# switch_board.net
KiCad netlist of a schematic drawn in EAGLE
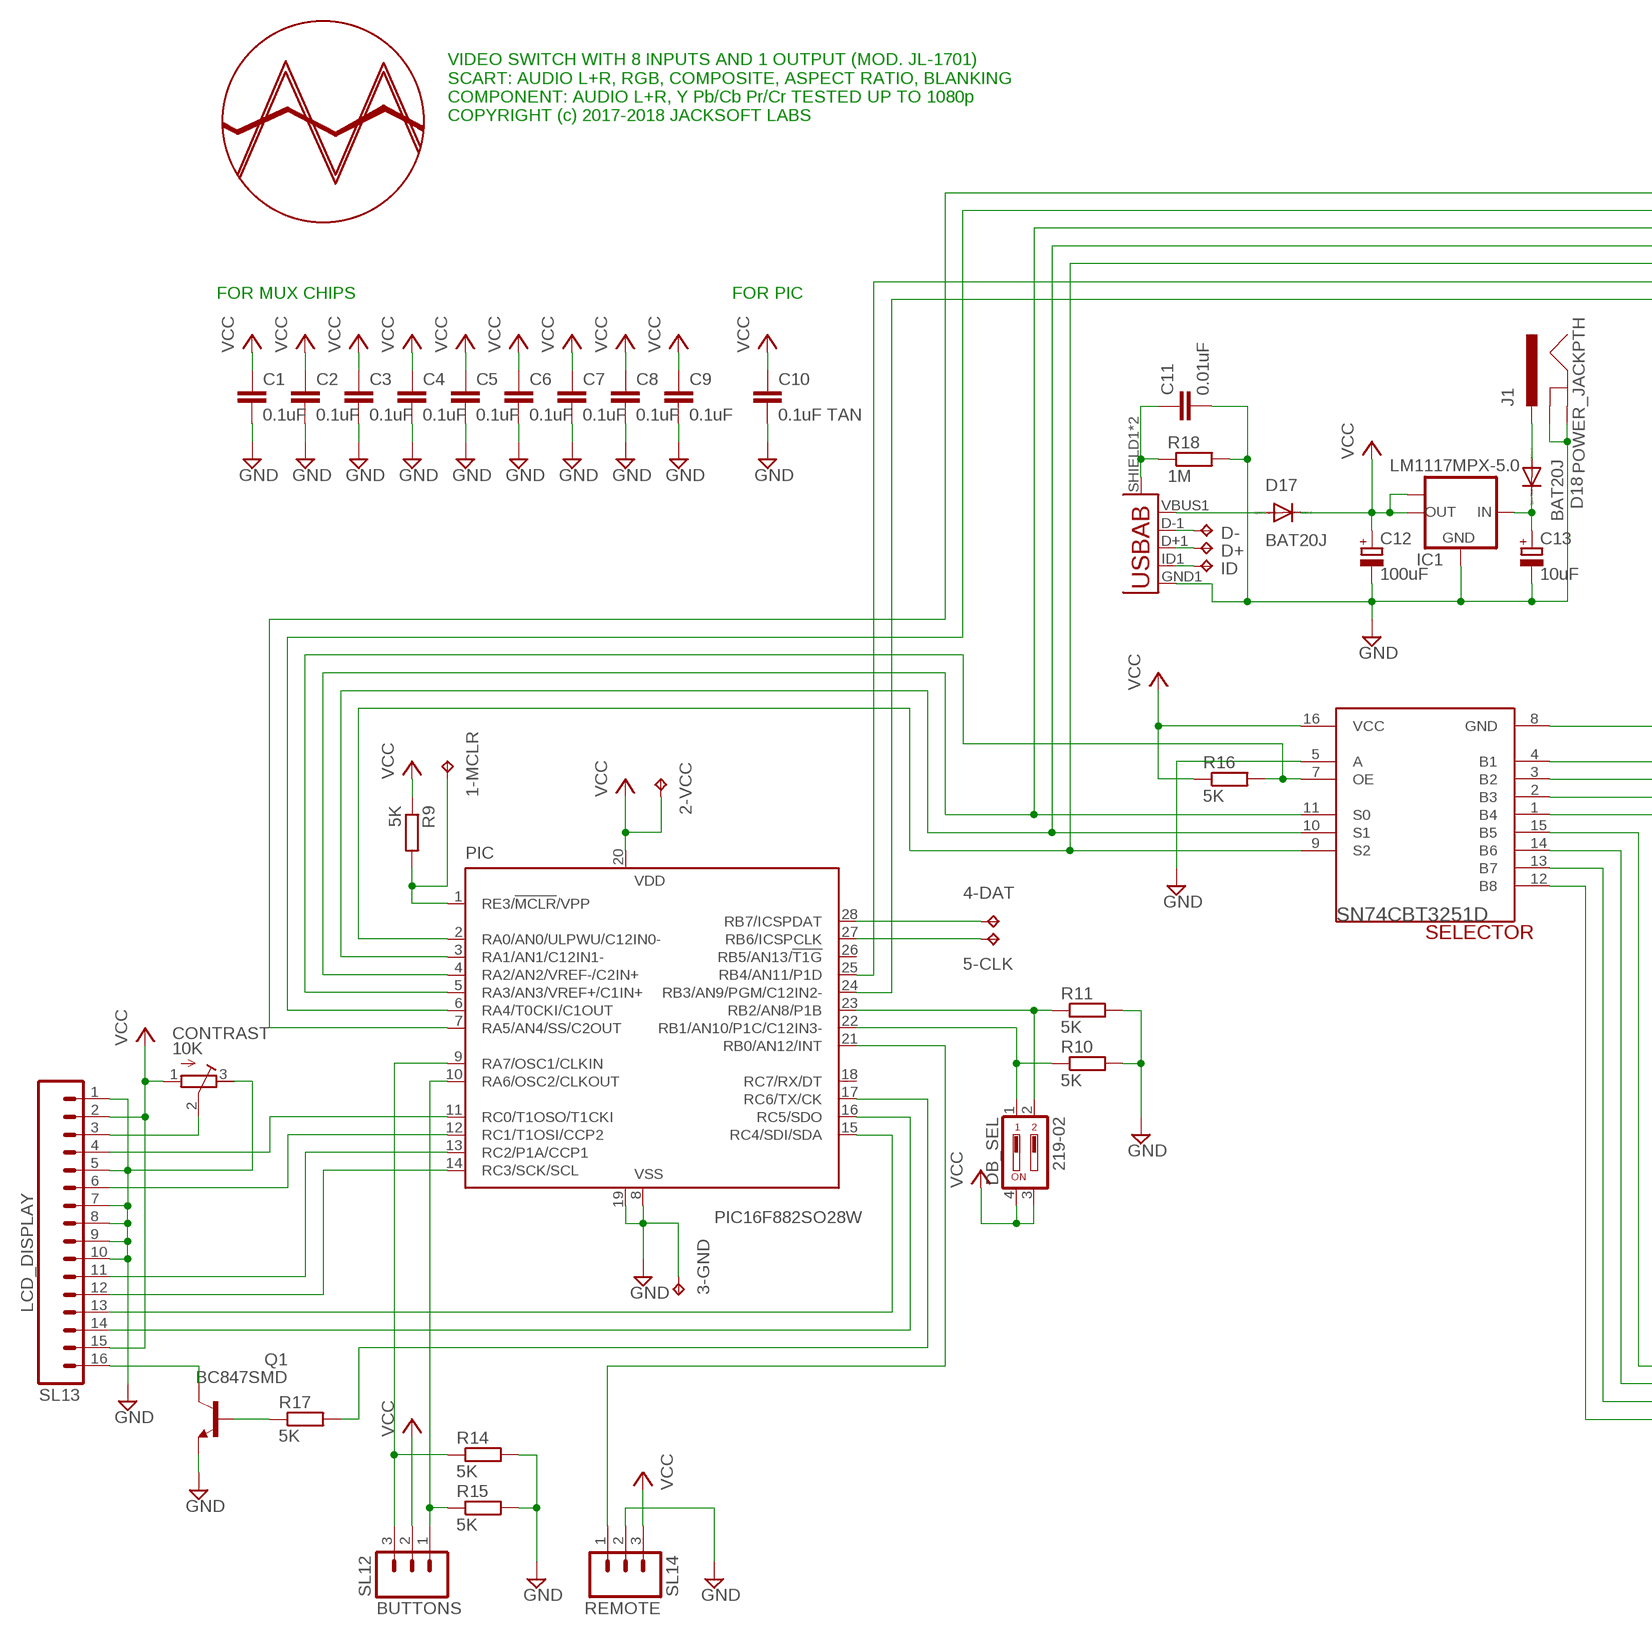
[diagram p0: schematic, sheet 1, part 1 of 2]
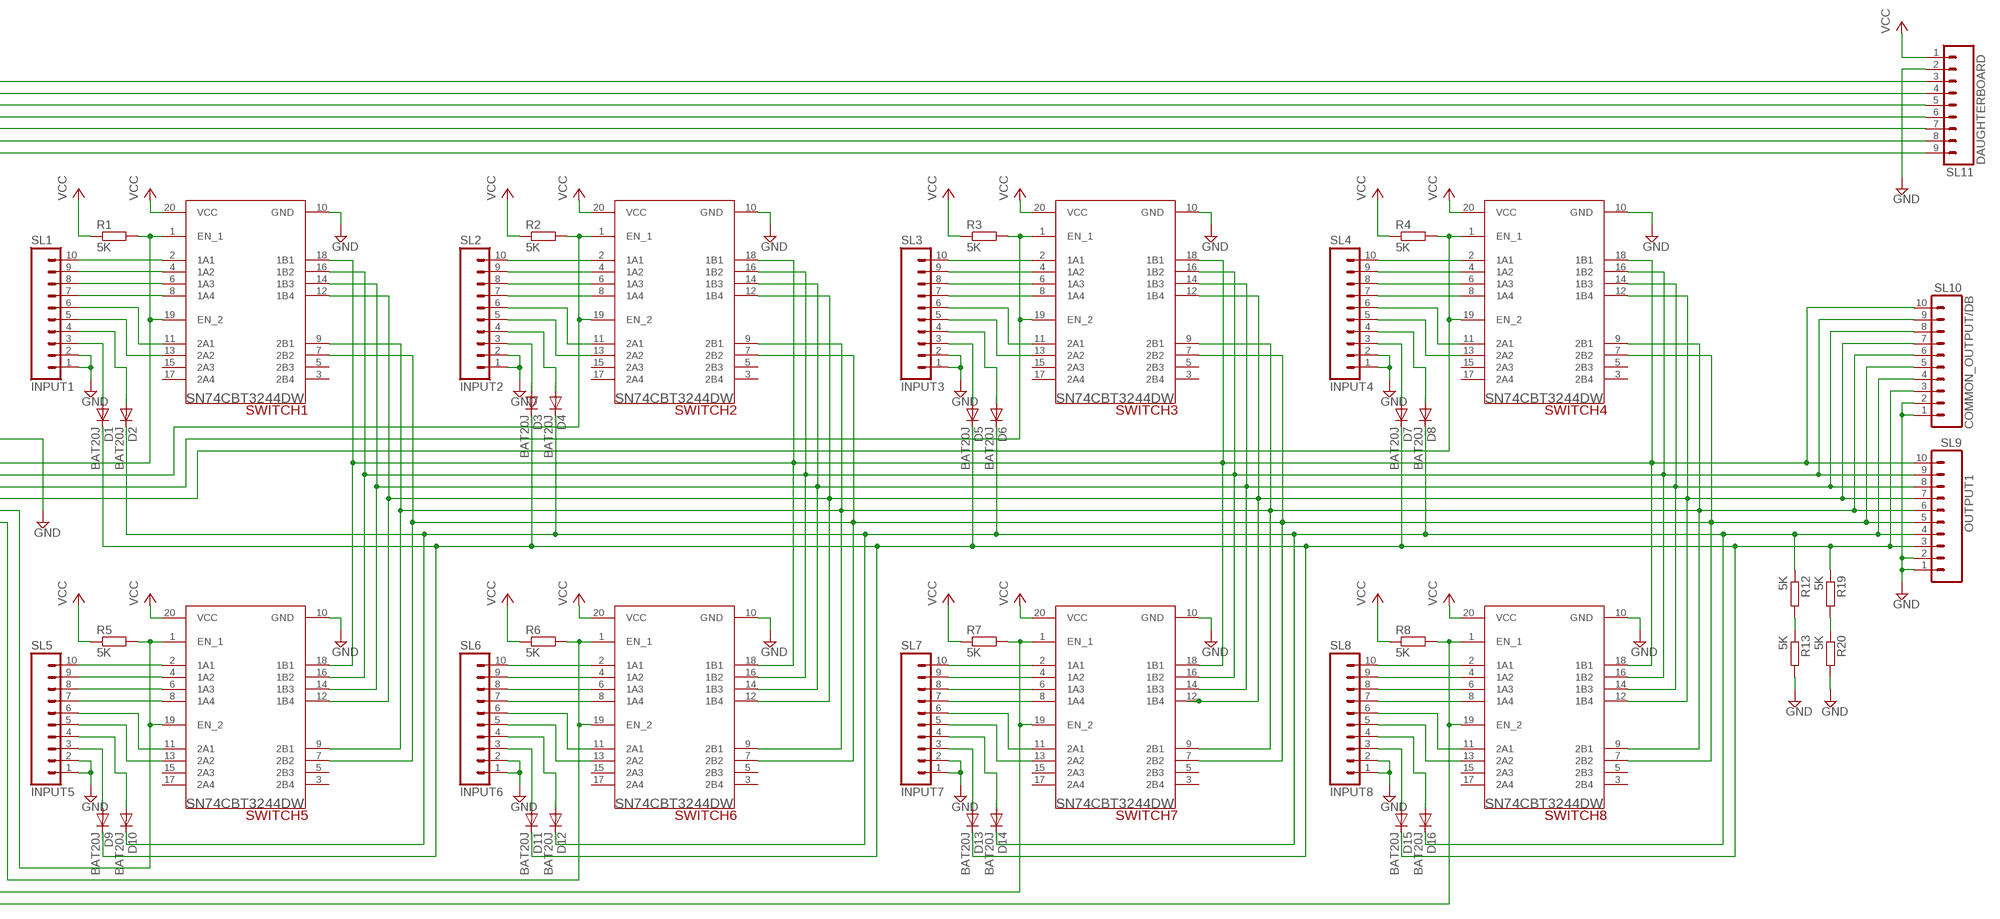
[diagram p1: schematic, sheet 1, part 2 of 2]

(export (version "E")
  (design (tool "Eeschema 10.0.6"))
  (components
    (comp (ref "1-MCLR")
      (value "TPB1,27")
      (footprint "eagle-import:B1,27")
      (libsource (lib "eagle-import") (part "TPB1,27"))
    )
    (comp (ref "2-VCC")
      (value "TPB1,27")
      (footprint "eagle-import:B1,27")
      (libsource (lib "eagle-import") (part "TPB1,27"))
    )
    (comp (ref "3-GND")
      (value "TPB1,27")
      (footprint "eagle-import:B1,27")
      (libsource (lib "eagle-import") (part "TPB1,27"))
    )
    (comp (ref "4-DAT")
      (value "TPB1,27")
      (footprint "eagle-import:B1,27")
      (libsource (lib "eagle-import") (part "TPB1,27"))
    )
    (comp (ref "5-CLK")
      (value "TPB1,27")
      (footprint "eagle-import:B1,27")
      (libsource (lib "eagle-import") (part "TPB1,27"))
    )
    (comp (ref "C1")
      (value "0.1uF")
      (footprint "eagle-import:C0603")
      (libsource (lib "eagle-import") (part "C-EUC0603"))
    )
    (comp (ref "C2")
      (value "0.1uF")
      (footprint "eagle-import:C0603")
      (libsource (lib "eagle-import") (part "C-EUC0603"))
    )
    (comp (ref "C3")
      (value "0.1uF")
      (footprint "eagle-import:C0603")
      (libsource (lib "eagle-import") (part "C-EUC0603"))
    )
    (comp (ref "C4")
      (value "0.1uF")
      (footprint "eagle-import:C0603")
      (libsource (lib "eagle-import") (part "C-EUC0603"))
    )
    (comp (ref "C5")
      (value "0.1uF")
      (footprint "eagle-import:C0603")
      (libsource (lib "eagle-import") (part "C-EUC0603"))
    )
    (comp (ref "C6")
      (value "0.1uF")
      (footprint "eagle-import:C0603")
      (libsource (lib "eagle-import") (part "C-EUC0603"))
    )
    (comp (ref "C7")
      (value "0.1uF")
      (footprint "eagle-import:C0603")
      (libsource (lib "eagle-import") (part "C-EUC0603"))
    )
    (comp (ref "C8")
      (value "0.1uF")
      (footprint "eagle-import:C0603")
      (libsource (lib "eagle-import") (part "C-EUC0603"))
    )
    (comp (ref "C9")
      (value "0.1uF")
      (footprint "eagle-import:C0603")
      (libsource (lib "eagle-import") (part "C-EUC0603"))
    )
    (comp (ref "C10")
      (value "0.1uF TAN")
      (footprint "eagle-import:C3216")
      (libsource (lib "eagle-import") (part "C-EUC3216"))
    )
    (comp (ref "C11")
      (value "0.01uF")
      (footprint "eagle-import:C0603")
      (libsource (lib "eagle-import") (part "C-EUC0603"))
    )
    (comp (ref "C12")
      (value "100uF")
      (footprint "eagle-import:153CLV-0405")
      (libsource (lib "eagle-import") (part "CPOL-EU153CLV-0405"))
    )
    (comp (ref "C13")
      (value "10uF")
      (footprint "eagle-import:153CLV-0405")
      (libsource (lib "eagle-import") (part "CPOL-EU153CLV-0405"))
    )
    (comp (ref "CONTRAST")
      (value "10K")
      (footprint "eagle-import:RTRIM3304W")
      (libsource (lib "eagle-import") (part "R-TRIMM3304W"))
    )
    (comp (ref "D+")
      (value "TPTP06R")
      (footprint "eagle-import:TP06R")
      (libsource (lib "eagle-import") (part "TPTP06R"))
    )
    (comp (ref "D-")
      (value "TPTP06R")
      (footprint "eagle-import:TP06R")
      (libsource (lib "eagle-import") (part "TPTP06R"))
    )
    (comp (ref "D1")
      (value "BAT20J")
      (footprint "eagle-import:SOD323-W")
      (libsource (lib "eagle-import") (part "DIODE-SOD323-W"))
    )
    (comp (ref "D2")
      (value "BAT20J")
      (footprint "eagle-import:SOD323-W")
      (libsource (lib "eagle-import") (part "DIODE-SOD323-W"))
    )
    (comp (ref "D3")
      (value "BAT20J")
      (footprint "eagle-import:SOD323-W")
      (libsource (lib "eagle-import") (part "DIODE-SOD323-W"))
    )
    (comp (ref "D4")
      (value "BAT20J")
      (footprint "eagle-import:SOD323-W")
      (libsource (lib "eagle-import") (part "DIODE-SOD323-W"))
    )
    (comp (ref "D5")
      (value "BAT20J")
      (footprint "eagle-import:SOD323-W")
      (libsource (lib "eagle-import") (part "DIODE-SOD323-W"))
    )
    (comp (ref "D6")
      (value "BAT20J")
      (footprint "eagle-import:SOD323-W")
      (libsource (lib "eagle-import") (part "DIODE-SOD323-W"))
    )
    (comp (ref "D7")
      (value "BAT20J")
      (footprint "eagle-import:SOD323-W")
      (libsource (lib "eagle-import") (part "DIODE-SOD323-W"))
    )
    (comp (ref "D8")
      (value "BAT20J")
      (footprint "eagle-import:SOD323-W")
      (libsource (lib "eagle-import") (part "DIODE-SOD323-W"))
    )
    (comp (ref "D9")
      (value "BAT20J")
      (footprint "eagle-import:SOD323-W")
      (libsource (lib "eagle-import") (part "DIODE-SOD323-W"))
    )
    (comp (ref "D10")
      (value "BAT20J")
      (footprint "eagle-import:SOD323-W")
      (libsource (lib "eagle-import") (part "DIODE-SOD323-W"))
    )
    (comp (ref "D11")
      (value "BAT20J")
      (footprint "eagle-import:SOD323-W")
      (libsource (lib "eagle-import") (part "DIODE-SOD323-W"))
    )
    (comp (ref "D12")
      (value "BAT20J")
      (footprint "eagle-import:SOD323-W")
      (libsource (lib "eagle-import") (part "DIODE-SOD323-W"))
    )
    (comp (ref "D13")
      (value "BAT20J")
      (footprint "eagle-import:SOD323-W")
      (libsource (lib "eagle-import") (part "DIODE-SOD323-W"))
    )
    (comp (ref "D14")
      (value "BAT20J")
      (footprint "eagle-import:SOD323-W")
      (libsource (lib "eagle-import") (part "DIODE-SOD323-W"))
    )
    (comp (ref "D15")
      (value "BAT20J")
      (footprint "eagle-import:SOD323-W")
      (libsource (lib "eagle-import") (part "DIODE-SOD323-W"))
    )
    (comp (ref "D16")
      (value "BAT20J")
      (footprint "eagle-import:SOD323-W")
      (libsource (lib "eagle-import") (part "DIODE-SOD323-W"))
    )
    (comp (ref "D17")
      (value "BAT20J")
      (footprint "eagle-import:SOD323-W")
      (libsource (lib "eagle-import") (part "DIODE-SOD323-W"))
    )
    (comp (ref "D18")
      (value "BAT20J")
      (footprint "eagle-import:SOD323-W")
      (libsource (lib "eagle-import") (part "DIODE-SOD323-W"))
    )
    (comp (ref "DB_SEL")
      (value "219-02")
      (footprint "eagle-import:CTS-219-02")
      (libsource (lib "eagle-import") (part "219-02"))
    )
    (comp (ref "IC1")
      (value "LM1117MPX-5.0")
      (footprint "eagle-import:SOT223")
      (libsource (lib "eagle-import") (part "LM1117MPX-5.0"))
    )
    (comp (ref "ID")
      (value "TPTP06R")
      (footprint "eagle-import:TP06R")
      (libsource (lib "eagle-import") (part "TPTP06R"))
    )
    (comp (ref "J1")
      (value "POWER_JACKPTH")
      (footprint "eagle-import:POWER_JACK_PTH")
      (libsource (lib "eagle-import") (part "POWER_JACKPTH"))
    )
    (comp (ref "PIC")
      (value "PIC16F882SO28W")
      (footprint "eagle-import:16F882")
      (libsource (lib "eagle-import") (part "PIC16F882SO28W"))
    )
    (comp (ref "Q1")
      (value "BC847SMD")
      (footprint "eagle-import:SOT23")
      (libsource (lib "eagle-import") (part "BC847SMD"))
    )
    (comp (ref "R1")
      (value "5K")
      (footprint "eagle-import:R0603")
      (libsource (lib "eagle-import") (part "R-EU_R0603"))
    )
    (comp (ref "R2")
      (value "5K")
      (footprint "eagle-import:R0603")
      (libsource (lib "eagle-import") (part "R-EU_R0603"))
    )
    (comp (ref "R3")
      (value "5K")
      (footprint "eagle-import:R0603")
      (libsource (lib "eagle-import") (part "R-EU_R0603"))
    )
    (comp (ref "R4")
      (value "5K")
      (footprint "eagle-import:R0603")
      (libsource (lib "eagle-import") (part "R-EU_R0603"))
    )
    (comp (ref "R5")
      (value "5K")
      (footprint "eagle-import:R0603")
      (libsource (lib "eagle-import") (part "R-EU_R0603"))
    )
    (comp (ref "R6")
      (value "5K")
      (footprint "eagle-import:R0603")
      (libsource (lib "eagle-import") (part "R-EU_R0603"))
    )
    (comp (ref "R7")
      (value "5K")
      (footprint "eagle-import:R0603")
      (libsource (lib "eagle-import") (part "R-EU_R0603"))
    )
    (comp (ref "R8")
      (value "5K")
      (footprint "eagle-import:R0603")
      (libsource (lib "eagle-import") (part "R-EU_R0603"))
    )
    (comp (ref "R9")
      (value "5K")
      (footprint "eagle-import:R0603")
      (libsource (lib "eagle-import") (part "R-EU_R0603"))
    )
    (comp (ref "R10")
      (value "5K")
      (footprint "eagle-import:R0603")
      (libsource (lib "eagle-import") (part "R-EU_R0603"))
    )
    (comp (ref "R11")
      (value "5K")
      (footprint "eagle-import:R0603")
      (libsource (lib "eagle-import") (part "R-EU_R0603"))
    )
    (comp (ref "R12")
      (value "5K")
      (footprint "eagle-import:R0603")
      (libsource (lib "eagle-import") (part "R-EU_R0603"))
    )
    (comp (ref "R13")
      (value "5K")
      (footprint "eagle-import:R0603")
      (libsource (lib "eagle-import") (part "R-EU_R0603"))
    )
    (comp (ref "R14")
      (value "5K")
      (footprint "eagle-import:R0603")
      (libsource (lib "eagle-import") (part "R-EU_R0603"))
    )
    (comp (ref "R15")
      (value "5K")
      (footprint "eagle-import:R0603")
      (libsource (lib "eagle-import") (part "R-EU_R0603"))
    )
    (comp (ref "R16")
      (value "5K")
      (footprint "eagle-import:R0603")
      (libsource (lib "eagle-import") (part "R-EU_R0603"))
    )
    (comp (ref "R17")
      (value "5K")
      (footprint "eagle-import:R0603")
      (libsource (lib "eagle-import") (part "R-EU_R0603"))
    )
    (comp (ref "R18")
      (value "1M")
      (footprint "eagle-import:R0603")
      (libsource (lib "eagle-import") (part "R-EU_R0603"))
    )
    (comp (ref "R19")
      (value "5K")
      (footprint "eagle-import:R0603")
      (libsource (lib "eagle-import") (part "R-EU_R0603"))
    )
    (comp (ref "R20")
      (value "5K")
      (footprint "eagle-import:R0603")
      (libsource (lib "eagle-import") (part "R-EU_R0603"))
    )
    (comp (ref "SELECTOR")
      (value "SN74CBT3251D")
      (footprint "eagle-import:SOIC127P1032X265-16N")
      (libsource (lib "eagle-import") (part "SN74CBT3251D"))
    )
    (comp (ref "SL1")
      (value "INPUT1")
      (footprint "eagle-import:10P")
      (libsource (lib "eagle-import") (part "M10"))
    )
    (comp (ref "SL2")
      (value "INPUT2")
      (footprint "eagle-import:10P")
      (libsource (lib "eagle-import") (part "M10"))
    )
    (comp (ref "SL3")
      (value "INPUT3")
      (footprint "eagle-import:10P")
      (libsource (lib "eagle-import") (part "M10"))
    )
    (comp (ref "SL4")
      (value "INPUT4")
      (footprint "eagle-import:10P")
      (libsource (lib "eagle-import") (part "M10"))
    )
    (comp (ref "SL5")
      (value "INPUT5")
      (footprint "eagle-import:10P")
      (libsource (lib "eagle-import") (part "M10"))
    )
    (comp (ref "SL6")
      (value "INPUT6")
      (footprint "eagle-import:10P")
      (libsource (lib "eagle-import") (part "M10"))
    )
    (comp (ref "SL7")
      (value "INPUT7")
      (footprint "eagle-import:10P")
      (libsource (lib "eagle-import") (part "M10"))
    )
    (comp (ref "SL8")
      (value "INPUT8")
      (footprint "eagle-import:10P")
      (libsource (lib "eagle-import") (part "M10"))
    )
    (comp (ref "SL9")
      (value "OUTPUT1")
      (footprint "eagle-import:10P")
      (libsource (lib "eagle-import") (part "M10"))
    )
    (comp (ref "SL10")
      (value "COMMON_OUTPUT/DB")
      (footprint "eagle-import:10P")
      (libsource (lib "eagle-import") (part "M10"))
    )
    (comp (ref "SL11")
      (value "DAUGHTERBOARD")
      (footprint "eagle-import:09P")
      (libsource (lib "eagle-import") (part "M09"))
    )
    (comp (ref "SL12")
      (value "BUTTONS")
      (footprint "eagle-import:03P")
      (libsource (lib "eagle-import") (part "M03"))
    )
    (comp (ref "SL13")
      (value "LCD_DISPLAY")
      (footprint "eagle-import:16P")
      (libsource (lib "eagle-import") (part "M16"))
    )
    (comp (ref "SL14")
      (value "REMOTE")
      (footprint "eagle-import:03P")
      (libsource (lib "eagle-import") (part "M03"))
    )
    (comp (ref "SWITCH1")
      (value "SN74CBT3244DW")
      (footprint "eagle-import:SOIC127P1032X265-20N")
      (libsource (lib "eagle-import") (part "SN74CBT3244DW"))
    )
    (comp (ref "SWITCH2")
      (value "SN74CBT3244DW")
      (footprint "eagle-import:SOIC127P1032X265-20N")
      (libsource (lib "eagle-import") (part "SN74CBT3244DW"))
    )
    (comp (ref "SWITCH3")
      (value "SN74CBT3244DW")
      (footprint "eagle-import:SOIC127P1032X265-20N")
      (libsource (lib "eagle-import") (part "SN74CBT3244DW"))
    )
    (comp (ref "SWITCH4")
      (value "SN74CBT3244DW")
      (footprint "eagle-import:SOIC127P1032X265-20N")
      (libsource (lib "eagle-import") (part "SN74CBT3244DW"))
    )
    (comp (ref "SWITCH5")
      (value "SN74CBT3244DW")
      (footprint "eagle-import:SOIC127P1032X265-20N")
      (libsource (lib "eagle-import") (part "SN74CBT3244DW"))
    )
    (comp (ref "SWITCH6")
      (value "SN74CBT3244DW")
      (footprint "eagle-import:SOIC127P1032X265-20N")
      (libsource (lib "eagle-import") (part "SN74CBT3244DW"))
    )
    (comp (ref "SWITCH7")
      (value "SN74CBT3244DW")
      (footprint "eagle-import:SOIC127P1032X265-20N")
      (libsource (lib "eagle-import") (part "SN74CBT3244DW"))
    )
    (comp (ref "SWITCH8")
      (value "SN74CBT3244DW")
      (footprint "eagle-import:SOIC127P1032X265-20N")
      (libsource (lib "eagle-import") (part "SN74CBT3244DW"))
    )
    (comp (ref "U$1")
      (value "JACKSOFTLABS-LOGOLONGTEXT")
      (footprint "eagle-import:LOGO-LONGTEXT")
      (libsource (lib "eagle-import") (part "JACKSOFTLABS-LOGOLONGTEXT"))
    )
    (comp (ref "USB")
      (value "USB_POWER")
      (footprint "eagle-import:USB-MICRO-SMD")
      (libsource (lib "eagle-import") (part "MICROUSB{dblquote}{dblquote}"))
    )
  )
  (nets
    (net (code "1") (name "GND") (class "Default")
      (node (ref "3-GND") (pin "TP") (pinfunction "TP_TP") (pintype "input"))
      (node (ref "C1") (pin "2") (pinfunction "2_2") (pintype "passive"))
      (node (ref "C10") (pin "2") (pinfunction "2_2") (pintype "passive"))
      (node (ref "C11") (pin "2") (pinfunction "2_2") (pintype "passive"))
      (node (ref "C12") (pin "-") (pinfunction "-_-") (pintype "passive"))
      (node (ref "C13") (pin "-") (pinfunction "-_-") (pintype "passive"))
      (node (ref "C2") (pin "2") (pinfunction "2_2") (pintype "passive"))
      (node (ref "C3") (pin "2") (pinfunction "2_2") (pintype "passive"))
      (node (ref "C4") (pin "2") (pinfunction "2_2") (pintype "passive"))
      (node (ref "C5") (pin "2") (pinfunction "2_2") (pintype "passive"))
      (node (ref "C6") (pin "2") (pinfunction "2_2") (pintype "passive"))
      (node (ref "C7") (pin "2") (pinfunction "2_2") (pintype "passive"))
      (node (ref "C8") (pin "2") (pinfunction "2_2") (pintype "passive"))
      (node (ref "C9") (pin "2") (pinfunction "2_2") (pintype "passive"))
      (node (ref "CONTRAST") (pin "3") (pinfunction "E_3") (pintype "passive"))
      (node (ref "IC1") (pin "1") (pinfunction "GND_1") (pintype "input"))
      (node (ref "J1") (pin "GND") (pinfunction "GND_GND") (pintype "bidirectional"))
      (node (ref "J1") (pin "GNDBREAK") (pinfunction "GNDBREAK_GNDBREAK") (pintype "bidirectional"))
      (node (ref "PIC") (pin "19") (pinfunction "VSS_19") (pintype "power_in"))
      (node (ref "PIC") (pin "8") (pinfunction "VSS_8") (pintype "power_in"))
      (node (ref "Q1") (pin "2") (pinfunction "E_2") (pintype "passive"))
      (node (ref "R10") (pin "2") (pinfunction "2_2") (pintype "passive"))
      (node (ref "R11") (pin "2") (pinfunction "2_2") (pintype "passive"))
      (node (ref "R13") (pin "2") (pinfunction "2_2") (pintype "passive"))
      (node (ref "R14") (pin "2") (pinfunction "2_2") (pintype "passive"))
      (node (ref "R15") (pin "2") (pinfunction "2_2") (pintype "passive"))
      (node (ref "R18") (pin "2") (pinfunction "2_2") (pintype "passive"))
      (node (ref "R20") (pin "2") (pinfunction "2_2") (pintype "passive"))
      (node (ref "SELECTOR") (pin "5") (pinfunction "A_5") (pintype "input"))
      (node (ref "SELECTOR") (pin "8") (pinfunction "GND_8") (pintype "input"))
      (node (ref "SL1") (pin "1") (pinfunction "1_1") (pintype "passive"))
      (node (ref "SL1") (pin "2") (pinfunction "2_2") (pintype "passive"))
      (node (ref "SL10") (pin "1") (pinfunction "1_1") (pintype "passive"))
      (node (ref "SL10") (pin "2") (pinfunction "2_2") (pintype "passive"))
      (node (ref "SL11") (pin "2") (pinfunction "2_2") (pintype "passive"))
      (node (ref "SL13") (pin "1") (pinfunction "1_1") (pintype "passive"))
      (node (ref "SL13") (pin "10") (pinfunction "10_10") (pintype "passive"))
      (node (ref "SL13") (pin "5") (pinfunction "5_5") (pintype "passive"))
      (node (ref "SL13") (pin "7") (pinfunction "7_7") (pintype "passive"))
      (node (ref "SL13") (pin "8") (pinfunction "8_8") (pintype "passive"))
      (node (ref "SL13") (pin "9") (pinfunction "9_9") (pintype "passive"))
      (node (ref "SL14") (pin "2") (pinfunction "2_2") (pintype "passive"))
      (node (ref "SL2") (pin "1") (pinfunction "1_1") (pintype "passive"))
      (node (ref "SL2") (pin "2") (pinfunction "2_2") (pintype "passive"))
      (node (ref "SL3") (pin "1") (pinfunction "1_1") (pintype "passive"))
      (node (ref "SL3") (pin "2") (pinfunction "2_2") (pintype "passive"))
      (node (ref "SL4") (pin "1") (pinfunction "1_1") (pintype "passive"))
      (node (ref "SL4") (pin "2") (pinfunction "2_2") (pintype "passive"))
      (node (ref "SL5") (pin "1") (pinfunction "1_1") (pintype "passive"))
      (node (ref "SL5") (pin "2") (pinfunction "2_2") (pintype "passive"))
      (node (ref "SL6") (pin "1") (pinfunction "1_1") (pintype "passive"))
      (node (ref "SL6") (pin "2") (pinfunction "2_2") (pintype "passive"))
      (node (ref "SL7") (pin "1") (pinfunction "1_1") (pintype "passive"))
      (node (ref "SL7") (pin "2") (pinfunction "2_2") (pintype "passive"))
      (node (ref "SL8") (pin "1") (pinfunction "1_1") (pintype "passive"))
      (node (ref "SL8") (pin "2") (pinfunction "2_2") (pintype "passive"))
      (node (ref "SL9") (pin "1") (pinfunction "1_1") (pintype "passive"))
      (node (ref "SL9") (pin "2") (pinfunction "2_2") (pintype "passive"))
      (node (ref "SWITCH1") (pin "10") (pinfunction "GND_10") (pintype "input"))
      (node (ref "SWITCH2") (pin "10") (pinfunction "GND_10") (pintype "input"))
      (node (ref "SWITCH3") (pin "10") (pinfunction "GND_10") (pintype "input"))
      (node (ref "SWITCH4") (pin "10") (pinfunction "GND_10") (pintype "input"))
      (node (ref "SWITCH5") (pin "10") (pinfunction "GND_10") (pintype "input"))
      (node (ref "SWITCH6") (pin "10") (pinfunction "GND_10") (pintype "input"))
      (node (ref "SWITCH7") (pin "10") (pinfunction "GND_10") (pintype "input"))
      (node (ref "SWITCH8") (pin "10") (pinfunction "GND_10") (pintype "input"))
      (node (ref "USB") (pin "GND1") (pinfunction "GND_GND1") (pintype "bidirectional"))
    )
    (net (code "2") (name "Net-(C11-Pad1)") (class "Default")
      (node (ref "C11") (pin "1") (pinfunction "1_1") (pintype "passive"))
      (node (ref "R18") (pin "1") (pinfunction "1_1") (pintype "passive"))
      (node (ref "USB") (pin "SHIELD1") (pinfunction "SHIELD_SHIELD1") (pintype "bidirectional"))
      (node (ref "USB") (pin "SHIELD2") (pinfunction "SHIELD_SHIELD2") (pintype "bidirectional"))
    )
    (net (code "3") (name "Net-(CONTRAST-S)") (class "Default")
      (node (ref "CONTRAST") (pin "2") (pinfunction "S_2") (pintype "passive"))
      (node (ref "SL13") (pin "3") (pinfunction "3_3") (pintype "passive"))
    )
    (net (code "4") (name "Net-(D1-PadA)") (class "Default")
      (node (ref "D1") (pin "A") (pinfunction "A_A") (pintype "passive"))
      (node (ref "SL1") (pin "3") (pinfunction "3_3") (pintype "passive"))
    )
    (net (code "5") (name "Net-(D1-PadC)") (class "Default")
      (node (ref "D1") (pin "C") (pinfunction "C_C") (pintype "passive"))
      (node (ref "D11") (pin "C") (pinfunction "C_C") (pintype "passive"))
      (node (ref "D13") (pin "C") (pinfunction "C_C") (pintype "passive"))
      (node (ref "D15") (pin "C") (pinfunction "C_C") (pintype "passive"))
      (node (ref "D3") (pin "C") (pinfunction "C_C") (pintype "passive"))
      (node (ref "D5") (pin "C") (pinfunction "C_C") (pintype "passive"))
      (node (ref "D7") (pin "C") (pinfunction "C_C") (pintype "passive"))
      (node (ref "D9") (pin "C") (pinfunction "C_C") (pintype "passive"))
      (node (ref "R19") (pin "1") (pinfunction "1_1") (pintype "passive"))
      (node (ref "SL10") (pin "3") (pinfunction "3_3") (pintype "passive"))
      (node (ref "SL9") (pin "3") (pinfunction "3_3") (pintype "passive"))
    )
    (net (code "6") (name "Net-(D2-PadA)") (class "Default")
      (node (ref "D2") (pin "A") (pinfunction "A_A") (pintype "passive"))
      (node (ref "SL1") (pin "4") (pinfunction "4_4") (pintype "passive"))
    )
    (net (code "7") (name "Net-(D3-PadA)") (class "Default")
      (node (ref "D3") (pin "A") (pinfunction "A_A") (pintype "passive"))
      (node (ref "SL2") (pin "3") (pinfunction "3_3") (pintype "passive"))
    )
    (net (code "8") (name "Net-(D4-PadA)") (class "Default")
      (node (ref "D4") (pin "A") (pinfunction "A_A") (pintype "passive"))
      (node (ref "SL2") (pin "4") (pinfunction "4_4") (pintype "passive"))
    )
    (net (code "9") (name "Net-(D5-PadA)") (class "Default")
      (node (ref "D5") (pin "A") (pinfunction "A_A") (pintype "passive"))
      (node (ref "SL3") (pin "3") (pinfunction "3_3") (pintype "passive"))
    )
    (net (code "10") (name "Net-(D6-PadA)") (class "Default")
      (node (ref "D6") (pin "A") (pinfunction "A_A") (pintype "passive"))
      (node (ref "SL3") (pin "4") (pinfunction "4_4") (pintype "passive"))
    )
    (net (code "11") (name "Net-(D7-PadA)") (class "Default")
      (node (ref "D7") (pin "A") (pinfunction "A_A") (pintype "passive"))
      (node (ref "SL4") (pin "3") (pinfunction "3_3") (pintype "passive"))
    )
    (net (code "12") (name "Net-(D8-PadA)") (class "Default")
      (node (ref "D8") (pin "A") (pinfunction "A_A") (pintype "passive"))
      (node (ref "SL4") (pin "4") (pinfunction "4_4") (pintype "passive"))
    )
    (net (code "13") (name "Net-(D9-PadA)") (class "Default")
      (node (ref "D9") (pin "A") (pinfunction "A_A") (pintype "passive"))
      (node (ref "SL5") (pin "3") (pinfunction "3_3") (pintype "passive"))
    )
    (net (code "14") (name "Net-(D10-PadA)") (class "Default")
      (node (ref "D10") (pin "A") (pinfunction "A_A") (pintype "passive"))
      (node (ref "SL5") (pin "4") (pinfunction "4_4") (pintype "passive"))
    )
    (net (code "15") (name "Net-(D10-PadC)") (class "Default")
      (node (ref "D10") (pin "C") (pinfunction "C_C") (pintype "passive"))
      (node (ref "D12") (pin "C") (pinfunction "C_C") (pintype "passive"))
      (node (ref "D14") (pin "C") (pinfunction "C_C") (pintype "passive"))
      (node (ref "D16") (pin "C") (pinfunction "C_C") (pintype "passive"))
      (node (ref "D2") (pin "C") (pinfunction "C_C") (pintype "passive"))
      (node (ref "D4") (pin "C") (pinfunction "C_C") (pintype "passive"))
      (node (ref "D6") (pin "C") (pinfunction "C_C") (pintype "passive"))
      (node (ref "D8") (pin "C") (pinfunction "C_C") (pintype "passive"))
      (node (ref "R12") (pin "1") (pinfunction "1_1") (pintype "passive"))
      (node (ref "SL10") (pin "4") (pinfunction "4_4") (pintype "passive"))
      (node (ref "SL9") (pin "4") (pinfunction "4_4") (pintype "passive"))
    )
    (net (code "16") (name "Net-(D11-PadA)") (class "Default")
      (node (ref "D11") (pin "A") (pinfunction "A_A") (pintype "passive"))
      (node (ref "SL6") (pin "3") (pinfunction "3_3") (pintype "passive"))
    )
    (net (code "17") (name "Net-(D12-PadA)") (class "Default")
      (node (ref "D12") (pin "A") (pinfunction "A_A") (pintype "passive"))
      (node (ref "SL6") (pin "4") (pinfunction "4_4") (pintype "passive"))
    )
    (net (code "18") (name "Net-(D13-PadA)") (class "Default")
      (node (ref "D13") (pin "A") (pinfunction "A_A") (pintype "passive"))
      (node (ref "SL7") (pin "3") (pinfunction "3_3") (pintype "passive"))
    )
    (net (code "19") (name "Net-(D14-PadA)") (class "Default")
      (node (ref "D14") (pin "A") (pinfunction "A_A") (pintype "passive"))
      (node (ref "SL7") (pin "4") (pinfunction "4_4") (pintype "passive"))
    )
    (net (code "20") (name "Net-(D15-PadA)") (class "Default")
      (node (ref "D15") (pin "A") (pinfunction "A_A") (pintype "passive"))
      (node (ref "SL8") (pin "3") (pinfunction "3_3") (pintype "passive"))
    )
    (net (code "21") (name "Net-(D16-PadA)") (class "Default")
      (node (ref "D16") (pin "A") (pinfunction "A_A") (pintype "passive"))
      (node (ref "SL8") (pin "4") (pinfunction "4_4") (pintype "passive"))
    )
    (net (code "22") (name "Net-(D18-PadA)") (class "Default")
      (node (ref "D18") (pin "A") (pinfunction "A_A") (pintype "passive"))
      (node (ref "J1") (pin "PWR") (pinfunction "PWR_PWR") (pintype "bidirectional"))
    )
    (net (code "23") (name "Net-(IC1-IN)") (class "Default")
      (node (ref "C13") (pin "+") (pinfunction "+_+") (pintype "passive"))
      (node (ref "D18") (pin "C") (pinfunction "C_C") (pintype "passive"))
      (node (ref "IC1") (pin "3") (pinfunction "IN_3") (pintype "input"))
    )
    (net (code "24") (name "Net-(PIC-RA0{slash}AN0{slash}ULPWU{slash}C12IN0-)") (class "Default")
      (node (ref "PIC") (pin "2") (pinfunction "RA0/AN0/ULPWU/C12IN0-_2") (pintype "bidirectional"))
      (node (ref "SELECTOR") (pin "9") (pinfunction "S2_9") (pintype "input"))
      (node (ref "SL11") (pin "7") (pinfunction "7_7") (pintype "passive"))
    )
    (net (code "25") (name "Net-(PIC-RA1{slash}AN1{slash}C12IN1-)") (class "Default")
      (node (ref "PIC") (pin "3") (pinfunction "RA1/AN1/C12IN1-_3") (pintype "bidirectional"))
      (node (ref "SELECTOR") (pin "10") (pinfunction "S1_10") (pintype "input"))
      (node (ref "SL11") (pin "6") (pinfunction "6_6") (pintype "passive"))
    )
    (net (code "26") (name "Net-(PIC-RA2{slash}AN2{slash}VREF-{slash}C2IN+)") (class "Default")
      (node (ref "PIC") (pin "4") (pinfunction "RA2/AN2/VREF-/C2IN+_4") (pintype "bidirectional"))
      (node (ref "SELECTOR") (pin "11") (pinfunction "S0_11") (pintype "input"))
      (node (ref "SL11") (pin "5") (pinfunction "5_5") (pintype "passive"))
    )
    (net (code "27") (name "Net-(PIC-RA3{slash}AN3{slash}VREF+{slash}C1IN+)") (class "Default")
      (node (ref "PIC") (pin "5") (pinfunction "RA3/AN3/VREF+/C1IN+_5") (pintype "bidirectional"))
      (node (ref "R16") (pin "2") (pinfunction "2_2") (pintype "passive"))
      (node (ref "SELECTOR") (pin "7") (pinfunction "OE_7") (pintype "input"))
    )
    (net (code "28") (name "Net-(PIC-RA4{slash}T0CKI{slash}C1OUT)") (class "Default")
      (node (ref "PIC") (pin "6") (pinfunction "RA4/T0CKI/C1OUT_6") (pintype "bidirectional"))
      (node (ref "SL11") (pin "4") (pinfunction "4_4") (pintype "passive"))
    )
    (net (code "29") (name "Net-(PIC-RA5{slash}AN4{slash}SS{slash}C2OUT)") (class "Default")
      (node (ref "PIC") (pin "7") (pinfunction "RA5/AN4/SS/C2OUT_7") (pintype "bidirectional"))
      (node (ref "SL11") (pin "3") (pinfunction "3_3") (pintype "passive"))
    )
    (net (code "30") (name "Net-(PIC-RA6{slash}OSC2{slash}CLKOUT)") (class "Default")
      (node (ref "PIC") (pin "10") (pinfunction "RA6/OSC2/CLKOUT_10") (pintype "output"))
      (node (ref "R15") (pin "1") (pinfunction "1_1") (pintype "passive"))
      (node (ref "SL12") (pin "1") (pinfunction "1_1") (pintype "passive"))
    )
    (net (code "31") (name "Net-(PIC-RA7{slash}OSC1{slash}CLKIN)") (class "Default")
      (node (ref "PIC") (pin "9") (pinfunction "RA7/OSC1/CLKIN_9") (pintype "input"))
      (node (ref "R14") (pin "1") (pinfunction "1_1") (pintype "passive"))
      (node (ref "SL12") (pin "3") (pinfunction "3_3") (pintype "passive"))
    )
    (net (code "32") (name "Net-(PIC-RB0{slash}AN12{slash}INT)") (class "Default")
      (node (ref "PIC") (pin "21") (pinfunction "RB0/AN12/INT_21") (pintype "bidirectional"))
      (node (ref "SL14") (pin "1") (pinfunction "1_1") (pintype "passive"))
    )
    (net (code "33") (name "Net-(PIC-RB1{slash}AN10{slash}P1C{slash}C12IN3-)") (class "Default")
      (node (ref "DB_SEL") (pin "1") (pinfunction "1_1") (pintype "passive"))
      (node (ref "PIC") (pin "22") (pinfunction "RB1/AN10/P1C/C12IN3-_22") (pintype "bidirectional"))
      (node (ref "R10") (pin "1") (pinfunction "1_1") (pintype "passive"))
    )
    (net (code "34") (name "Net-(PIC-RB2{slash}AN8{slash}P1B)") (class "Default")
      (node (ref "DB_SEL") (pin "2") (pinfunction "2_2") (pintype "passive"))
      (node (ref "PIC") (pin "23") (pinfunction "RB2/AN8/P1B_23") (pintype "bidirectional"))
      (node (ref "R11") (pin "1") (pinfunction "1_1") (pintype "passive"))
    )
    (net (code "35") (name "Net-(PIC-RB3{slash}AN9{slash}PGM{slash}C12IN2-)") (class "Default")
      (node (ref "PIC") (pin "24") (pinfunction "RB3/AN9/PGM/C12IN2-_24") (pintype "bidirectional"))
      (node (ref "SL11") (pin "9") (pinfunction "9_9") (pintype "passive"))
    )
    (net (code "36") (name "Net-(PIC-RB4{slash}AN11{slash}P1D)") (class "Default")
      (node (ref "PIC") (pin "25") (pinfunction "RB4/AN11/P1D_25") (pintype "bidirectional"))
      (node (ref "SL11") (pin "8") (pinfunction "8_8") (pintype "passive"))
    )
    (net (code "37") (name "Net-(PIC-RB6{slash}ICSPCLK)") (class "Default")
      (node (ref "5-CLK") (pin "TP") (pinfunction "TP_TP") (pintype "input"))
      (node (ref "PIC") (pin "27") (pinfunction "RB6/ICSPCLK_27") (pintype "bidirectional"))
    )
    (net (code "38") (name "Net-(PIC-RB7{slash}ICSPDAT)") (class "Default")
      (node (ref "4-DAT") (pin "TP") (pinfunction "TP_TP") (pintype "input"))
      (node (ref "PIC") (pin "28") (pinfunction "RB7/ICSPDAT_28") (pintype "bidirectional"))
    )
    (net (code "39") (name "Net-(PIC-RC0{slash}T1OSO{slash}T1CKI)") (class "Default")
      (node (ref "PIC") (pin "11") (pinfunction "RC0/T1OSO/T1CKI_11") (pintype "bidirectional"))
      (node (ref "SL13") (pin "4") (pinfunction "4_4") (pintype "passive"))
    )
    (net (code "40") (name "Net-(PIC-RC1{slash}T1OSI{slash}CCP2)") (class "Default")
      (node (ref "PIC") (pin "12") (pinfunction "RC1/T1OSI/CCP2_12") (pintype "bidirectional"))
      (node (ref "SL13") (pin "6") (pinfunction "6_6") (pintype "passive"))
    )
    (net (code "41") (name "Net-(PIC-RC2{slash}P1A{slash}CCP1)") (class "Default")
      (node (ref "PIC") (pin "13") (pinfunction "RC2/P1A/CCP1_13") (pintype "bidirectional"))
      (node (ref "SL13") (pin "11") (pinfunction "11_11") (pintype "passive"))
    )
    (net (code "42") (name "Net-(PIC-RC3{slash}SCK{slash}SCL)") (class "Default")
      (node (ref "PIC") (pin "14") (pinfunction "RC3/SCK/SCL_14") (pintype "bidirectional"))
      (node (ref "SL13") (pin "12") (pinfunction "12_12") (pintype "passive"))
    )
    (net (code "43") (name "Net-(PIC-RC4{slash}SDI{slash}SDA)") (class "Default")
      (node (ref "PIC") (pin "15") (pinfunction "RC4/SDI/SDA_15") (pintype "bidirectional"))
      (node (ref "SL13") (pin "13") (pinfunction "13_13") (pintype "passive"))
    )
    (net (code "44") (name "Net-(PIC-RC5{slash}SDO)") (class "Default")
      (node (ref "PIC") (pin "16") (pinfunction "RC5/SDO_16") (pintype "bidirectional"))
      (node (ref "SL13") (pin "14") (pinfunction "14_14") (pintype "passive"))
    )
    (net (code "45") (name "Net-(PIC-RC6{slash}TX{slash}CK)") (class "Default")
      (node (ref "PIC") (pin "17") (pinfunction "RC6/TX/CK_17") (pintype "bidirectional"))
      (node (ref "R17") (pin "2") (pinfunction "2_2") (pintype "passive"))
    )
    (net (code "46") (name "Net-(PIC-RE3{slash}~{MCLR}{slash}VPP)") (class "Default")
      (node (ref "1-MCLR") (pin "TP") (pinfunction "TP_TP") (pintype "input"))
      (node (ref "PIC") (pin "1") (pinfunction "RE3/~{MCLR}/VPP_1") (pintype "input"))
      (node (ref "R9") (pin "2") (pinfunction "2_2") (pintype "passive"))
    )
    (net (code "47") (name "Net-(Q1-B)") (class "Default")
      (node (ref "Q1") (pin "1") (pinfunction "B_1") (pintype "passive"))
      (node (ref "R17") (pin "1") (pinfunction "1_1") (pintype "passive"))
    )
    (net (code "48") (name "Net-(Q1-C)") (class "Default")
      (node (ref "Q1") (pin "3") (pinfunction "C_3") (pintype "passive"))
      (node (ref "SL13") (pin "16") (pinfunction "16_16") (pintype "passive"))
    )
    (net (code "49") (name "Net-(R12-Pad2)") (class "Default")
      (node (ref "R12") (pin "2") (pinfunction "2_2") (pintype "passive"))
      (node (ref "R13") (pin "1") (pinfunction "1_1") (pintype "passive"))
    )
    (net (code "50") (name "Net-(R19-Pad2)") (class "Default")
      (node (ref "R19") (pin "2") (pinfunction "2_2") (pintype "passive"))
      (node (ref "R20") (pin "1") (pinfunction "1_1") (pintype "passive"))
    )
    (net (code "51") (name "Net-(SELECTOR-B1)") (class "Default")
      (node (ref "R1") (pin "2") (pinfunction "2_2") (pintype "passive"))
      (node (ref "SELECTOR") (pin "4") (pinfunction "B1_4") (pintype "output"))
      (node (ref "SWITCH1") (pin "1") (pinfunction "EN_1_1") (pintype "input"))
      (node (ref "SWITCH1") (pin "19") (pinfunction "EN_2_19") (pintype "input"))
    )
    (net (code "52") (name "Net-(SELECTOR-B2)") (class "Default")
      (node (ref "R2") (pin "2") (pinfunction "2_2") (pintype "passive"))
      (node (ref "SELECTOR") (pin "3") (pinfunction "B2_3") (pintype "output"))
      (node (ref "SWITCH2") (pin "1") (pinfunction "EN_1_1") (pintype "input"))
      (node (ref "SWITCH2") (pin "19") (pinfunction "EN_2_19") (pintype "input"))
    )
    (net (code "53") (name "Net-(SELECTOR-B3)") (class "Default")
      (node (ref "R3") (pin "2") (pinfunction "2_2") (pintype "passive"))
      (node (ref "SELECTOR") (pin "2") (pinfunction "B3_2") (pintype "output"))
      (node (ref "SWITCH3") (pin "1") (pinfunction "EN_1_1") (pintype "input"))
      (node (ref "SWITCH3") (pin "19") (pinfunction "EN_2_19") (pintype "input"))
    )
    (net (code "54") (name "Net-(SELECTOR-B4)") (class "Default")
      (node (ref "R4") (pin "2") (pinfunction "2_2") (pintype "passive"))
      (node (ref "SELECTOR") (pin "1") (pinfunction "B4_1") (pintype "output"))
      (node (ref "SWITCH4") (pin "1") (pinfunction "EN_1_1") (pintype "input"))
      (node (ref "SWITCH4") (pin "19") (pinfunction "EN_2_19") (pintype "input"))
    )
    (net (code "55") (name "Net-(SELECTOR-B5)") (class "Default")
      (node (ref "R5") (pin "2") (pinfunction "2_2") (pintype "passive"))
      (node (ref "SELECTOR") (pin "15") (pinfunction "B5_15") (pintype "output"))
      (node (ref "SWITCH5") (pin "1") (pinfunction "EN_1_1") (pintype "input"))
      (node (ref "SWITCH5") (pin "19") (pinfunction "EN_2_19") (pintype "input"))
    )
    (net (code "56") (name "Net-(SELECTOR-B6)") (class "Default")
      (node (ref "R6") (pin "2") (pinfunction "2_2") (pintype "passive"))
      (node (ref "SELECTOR") (pin "14") (pinfunction "B6_14") (pintype "output"))
      (node (ref "SWITCH6") (pin "1") (pinfunction "EN_1_1") (pintype "input"))
      (node (ref "SWITCH6") (pin "19") (pinfunction "EN_2_19") (pintype "input"))
    )
    (net (code "57") (name "Net-(SELECTOR-B7)") (class "Default")
      (node (ref "R7") (pin "2") (pinfunction "2_2") (pintype "passive"))
      (node (ref "SELECTOR") (pin "13") (pinfunction "B7_13") (pintype "output"))
      (node (ref "SWITCH7") (pin "1") (pinfunction "EN_1_1") (pintype "input"))
      (node (ref "SWITCH7") (pin "19") (pinfunction "EN_2_19") (pintype "input"))
    )
    (net (code "58") (name "Net-(SELECTOR-B8)") (class "Default")
      (node (ref "R8") (pin "2") (pinfunction "2_2") (pintype "passive"))
      (node (ref "SELECTOR") (pin "12") (pinfunction "B8_12") (pintype "output"))
      (node (ref "SWITCH8") (pin "1") (pinfunction "EN_1_1") (pintype "input"))
      (node (ref "SWITCH8") (pin "19") (pinfunction "EN_2_19") (pintype "input"))
    )
    (net (code "59") (name "Net-(SWITCH1-1A1)") (class "Default")
      (node (ref "SL1") (pin "10") (pinfunction "10_10") (pintype "passive"))
      (node (ref "SWITCH1") (pin "2") (pinfunction "1A1_2") (pintype "input"))
    )
    (net (code "60") (name "Net-(SWITCH1-1A2)") (class "Default")
      (node (ref "SL1") (pin "9") (pinfunction "9_9") (pintype "passive"))
      (node (ref "SWITCH1") (pin "4") (pinfunction "1A2_4") (pintype "input"))
    )
    (net (code "61") (name "Net-(SWITCH1-1A3)") (class "Default")
      (node (ref "SL1") (pin "8") (pinfunction "8_8") (pintype "passive"))
      (node (ref "SWITCH1") (pin "6") (pinfunction "1A3_6") (pintype "input"))
    )
    (net (code "62") (name "Net-(SWITCH1-1A4)") (class "Default")
      (node (ref "SL1") (pin "7") (pinfunction "7_7") (pintype "passive"))
      (node (ref "SWITCH1") (pin "8") (pinfunction "1A4_8") (pintype "input"))
    )
    (net (code "63") (name "Net-(SWITCH1-1B1)") (class "Default")
      (node (ref "SL10") (pin "10") (pinfunction "10_10") (pintype "passive"))
      (node (ref "SL9") (pin "10") (pinfunction "10_10") (pintype "passive"))
      (node (ref "SWITCH1") (pin "18") (pinfunction "1B1_18") (pintype "output"))
      (node (ref "SWITCH2") (pin "18") (pinfunction "1B1_18") (pintype "output"))
      (node (ref "SWITCH3") (pin "18") (pinfunction "1B1_18") (pintype "output"))
      (node (ref "SWITCH4") (pin "18") (pinfunction "1B1_18") (pintype "output"))
      (node (ref "SWITCH5") (pin "18") (pinfunction "1B1_18") (pintype "output"))
      (node (ref "SWITCH6") (pin "18") (pinfunction "1B1_18") (pintype "output"))
      (node (ref "SWITCH7") (pin "18") (pinfunction "1B1_18") (pintype "output"))
      (node (ref "SWITCH8") (pin "18") (pinfunction "1B1_18") (pintype "output"))
    )
    (net (code "64") (name "Net-(SWITCH1-1B2)") (class "Default")
      (node (ref "SL10") (pin "9") (pinfunction "9_9") (pintype "passive"))
      (node (ref "SL9") (pin "9") (pinfunction "9_9") (pintype "passive"))
      (node (ref "SWITCH1") (pin "16") (pinfunction "1B2_16") (pintype "output"))
      (node (ref "SWITCH2") (pin "16") (pinfunction "1B2_16") (pintype "output"))
      (node (ref "SWITCH3") (pin "16") (pinfunction "1B2_16") (pintype "output"))
      (node (ref "SWITCH4") (pin "16") (pinfunction "1B2_16") (pintype "output"))
      (node (ref "SWITCH5") (pin "16") (pinfunction "1B2_16") (pintype "output"))
      (node (ref "SWITCH6") (pin "16") (pinfunction "1B2_16") (pintype "output"))
      (node (ref "SWITCH7") (pin "16") (pinfunction "1B2_16") (pintype "output"))
      (node (ref "SWITCH8") (pin "16") (pinfunction "1B2_16") (pintype "output"))
    )
    (net (code "65") (name "Net-(SWITCH1-1B3)") (class "Default")
      (node (ref "SL10") (pin "8") (pinfunction "8_8") (pintype "passive"))
      (node (ref "SL9") (pin "8") (pinfunction "8_8") (pintype "passive"))
      (node (ref "SWITCH1") (pin "14") (pinfunction "1B3_14") (pintype "output"))
      (node (ref "SWITCH2") (pin "14") (pinfunction "1B3_14") (pintype "output"))
      (node (ref "SWITCH3") (pin "14") (pinfunction "1B3_14") (pintype "output"))
      (node (ref "SWITCH4") (pin "14") (pinfunction "1B3_14") (pintype "output"))
      (node (ref "SWITCH5") (pin "14") (pinfunction "1B3_14") (pintype "output"))
      (node (ref "SWITCH6") (pin "14") (pinfunction "1B3_14") (pintype "output"))
      (node (ref "SWITCH7") (pin "14") (pinfunction "1B3_14") (pintype "output"))
      (node (ref "SWITCH8") (pin "14") (pinfunction "1B3_14") (pintype "output"))
    )
    (net (code "66") (name "Net-(SWITCH1-1B4)") (class "Default")
      (node (ref "SL10") (pin "7") (pinfunction "7_7") (pintype "passive"))
      (node (ref "SL9") (pin "7") (pinfunction "7_7") (pintype "passive"))
      (node (ref "SWITCH1") (pin "12") (pinfunction "1B4_12") (pintype "output"))
      (node (ref "SWITCH2") (pin "12") (pinfunction "1B4_12") (pintype "output"))
      (node (ref "SWITCH3") (pin "12") (pinfunction "1B4_12") (pintype "output"))
      (node (ref "SWITCH4") (pin "12") (pinfunction "1B4_12") (pintype "output"))
      (node (ref "SWITCH5") (pin "12") (pinfunction "1B4_12") (pintype "output"))
      (node (ref "SWITCH6") (pin "12") (pinfunction "1B4_12") (pintype "output"))
      (node (ref "SWITCH7") (pin "12") (pinfunction "1B4_12") (pintype "output"))
      (node (ref "SWITCH8") (pin "12") (pinfunction "1B4_12") (pintype "output"))
    )
    (net (code "67") (name "Net-(SWITCH1-2A1)") (class "Default")
      (node (ref "SL1") (pin "6") (pinfunction "6_6") (pintype "passive"))
      (node (ref "SWITCH1") (pin "11") (pinfunction "2A1_11") (pintype "input"))
    )
    (net (code "68") (name "Net-(SWITCH1-2A2)") (class "Default")
      (node (ref "SL1") (pin "5") (pinfunction "5_5") (pintype "passive"))
      (node (ref "SWITCH1") (pin "13") (pinfunction "2A2_13") (pintype "input"))
    )
    (net (code "69") (name "Net-(SWITCH1-2B1)") (class "Default")
      (node (ref "SL10") (pin "6") (pinfunction "6_6") (pintype "passive"))
      (node (ref "SL9") (pin "6") (pinfunction "6_6") (pintype "passive"))
      (node (ref "SWITCH1") (pin "9") (pinfunction "2B1_9") (pintype "output"))
      (node (ref "SWITCH2") (pin "9") (pinfunction "2B1_9") (pintype "output"))
      (node (ref "SWITCH3") (pin "9") (pinfunction "2B1_9") (pintype "output"))
      (node (ref "SWITCH4") (pin "9") (pinfunction "2B1_9") (pintype "output"))
      (node (ref "SWITCH5") (pin "9") (pinfunction "2B1_9") (pintype "output"))
      (node (ref "SWITCH6") (pin "9") (pinfunction "2B1_9") (pintype "output"))
      (node (ref "SWITCH7") (pin "9") (pinfunction "2B1_9") (pintype "output"))
      (node (ref "SWITCH8") (pin "9") (pinfunction "2B1_9") (pintype "output"))
    )
    (net (code "70") (name "Net-(SWITCH1-2B2)") (class "Default")
      (node (ref "SL10") (pin "5") (pinfunction "5_5") (pintype "passive"))
      (node (ref "SL9") (pin "5") (pinfunction "5_5") (pintype "passive"))
      (node (ref "SWITCH1") (pin "7") (pinfunction "2B2_7") (pintype "output"))
      (node (ref "SWITCH2") (pin "7") (pinfunction "2B2_7") (pintype "output"))
      (node (ref "SWITCH3") (pin "7") (pinfunction "2B2_7") (pintype "output"))
      (node (ref "SWITCH4") (pin "7") (pinfunction "2B2_7") (pintype "output"))
      (node (ref "SWITCH5") (pin "7") (pinfunction "2B2_7") (pintype "output"))
      (node (ref "SWITCH6") (pin "7") (pinfunction "2B2_7") (pintype "output"))
      (node (ref "SWITCH7") (pin "7") (pinfunction "2B2_7") (pintype "output"))
      (node (ref "SWITCH8") (pin "7") (pinfunction "2B2_7") (pintype "output"))
    )
    (net (code "71") (name "Net-(SWITCH2-1A1)") (class "Default")
      (node (ref "SL2") (pin "10") (pinfunction "10_10") (pintype "passive"))
      (node (ref "SWITCH2") (pin "2") (pinfunction "1A1_2") (pintype "input"))
    )
    (net (code "72") (name "Net-(SWITCH2-1A2)") (class "Default")
      (node (ref "SL2") (pin "9") (pinfunction "9_9") (pintype "passive"))
      (node (ref "SWITCH2") (pin "4") (pinfunction "1A2_4") (pintype "input"))
    )
    (net (code "73") (name "Net-(SWITCH2-1A3)") (class "Default")
      (node (ref "SL2") (pin "8") (pinfunction "8_8") (pintype "passive"))
      (node (ref "SWITCH2") (pin "6") (pinfunction "1A3_6") (pintype "input"))
    )
    (net (code "74") (name "Net-(SWITCH2-1A4)") (class "Default")
      (node (ref "SL2") (pin "7") (pinfunction "7_7") (pintype "passive"))
      (node (ref "SWITCH2") (pin "8") (pinfunction "1A4_8") (pintype "input"))
    )
    (net (code "75") (name "Net-(SWITCH2-2A1)") (class "Default")
      (node (ref "SL2") (pin "6") (pinfunction "6_6") (pintype "passive"))
      (node (ref "SWITCH2") (pin "11") (pinfunction "2A1_11") (pintype "input"))
    )
    (net (code "76") (name "Net-(SWITCH2-2A2)") (class "Default")
      (node (ref "SL2") (pin "5") (pinfunction "5_5") (pintype "passive"))
      (node (ref "SWITCH2") (pin "13") (pinfunction "2A2_13") (pintype "input"))
    )
    (net (code "77") (name "Net-(SWITCH3-1A1)") (class "Default")
      (node (ref "SL3") (pin "10") (pinfunction "10_10") (pintype "passive"))
      (node (ref "SWITCH3") (pin "2") (pinfunction "1A1_2") (pintype "input"))
    )
    (net (code "78") (name "Net-(SWITCH3-1A2)") (class "Default")
      (node (ref "SL3") (pin "9") (pinfunction "9_9") (pintype "passive"))
      (node (ref "SWITCH3") (pin "4") (pinfunction "1A2_4") (pintype "input"))
    )
    (net (code "79") (name "Net-(SWITCH3-1A3)") (class "Default")
      (node (ref "SL3") (pin "8") (pinfunction "8_8") (pintype "passive"))
      (node (ref "SWITCH3") (pin "6") (pinfunction "1A3_6") (pintype "input"))
    )
    (net (code "80") (name "Net-(SWITCH3-1A4)") (class "Default")
      (node (ref "SL3") (pin "7") (pinfunction "7_7") (pintype "passive"))
      (node (ref "SWITCH3") (pin "8") (pinfunction "1A4_8") (pintype "input"))
    )
    (net (code "81") (name "Net-(SWITCH3-2A1)") (class "Default")
      (node (ref "SL3") (pin "6") (pinfunction "6_6") (pintype "passive"))
      (node (ref "SWITCH3") (pin "11") (pinfunction "2A1_11") (pintype "input"))
    )
    (net (code "82") (name "Net-(SWITCH3-2A2)") (class "Default")
      (node (ref "SL3") (pin "5") (pinfunction "5_5") (pintype "passive"))
      (node (ref "SWITCH3") (pin "13") (pinfunction "2A2_13") (pintype "input"))
    )
    (net (code "83") (name "Net-(SWITCH4-1A1)") (class "Default")
      (node (ref "SL4") (pin "10") (pinfunction "10_10") (pintype "passive"))
      (node (ref "SWITCH4") (pin "2") (pinfunction "1A1_2") (pintype "input"))
    )
    (net (code "84") (name "Net-(SWITCH4-1A2)") (class "Default")
      (node (ref "SL4") (pin "9") (pinfunction "9_9") (pintype "passive"))
      (node (ref "SWITCH4") (pin "4") (pinfunction "1A2_4") (pintype "input"))
    )
    (net (code "85") (name "Net-(SWITCH4-1A3)") (class "Default")
      (node (ref "SL4") (pin "8") (pinfunction "8_8") (pintype "passive"))
      (node (ref "SWITCH4") (pin "6") (pinfunction "1A3_6") (pintype "input"))
    )
    (net (code "86") (name "Net-(SWITCH4-1A4)") (class "Default")
      (node (ref "SL4") (pin "7") (pinfunction "7_7") (pintype "passive"))
      (node (ref "SWITCH4") (pin "8") (pinfunction "1A4_8") (pintype "input"))
    )
    (net (code "87") (name "Net-(SWITCH4-2A1)") (class "Default")
      (node (ref "SL4") (pin "6") (pinfunction "6_6") (pintype "passive"))
      (node (ref "SWITCH4") (pin "11") (pinfunction "2A1_11") (pintype "input"))
    )
    (net (code "88") (name "Net-(SWITCH4-2A2)") (class "Default")
      (node (ref "SL4") (pin "5") (pinfunction "5_5") (pintype "passive"))
      (node (ref "SWITCH4") (pin "13") (pinfunction "2A2_13") (pintype "input"))
    )
    (net (code "89") (name "Net-(SWITCH5-1A1)") (class "Default")
      (node (ref "SL5") (pin "10") (pinfunction "10_10") (pintype "passive"))
      (node (ref "SWITCH5") (pin "2") (pinfunction "1A1_2") (pintype "input"))
    )
    (net (code "90") (name "Net-(SWITCH5-1A2)") (class "Default")
      (node (ref "SL5") (pin "9") (pinfunction "9_9") (pintype "passive"))
      (node (ref "SWITCH5") (pin "4") (pinfunction "1A2_4") (pintype "input"))
    )
    (net (code "91") (name "Net-(SWITCH5-1A3)") (class "Default")
      (node (ref "SL5") (pin "8") (pinfunction "8_8") (pintype "passive"))
      (node (ref "SWITCH5") (pin "6") (pinfunction "1A3_6") (pintype "input"))
    )
    (net (code "92") (name "Net-(SWITCH5-1A4)") (class "Default")
      (node (ref "SL5") (pin "7") (pinfunction "7_7") (pintype "passive"))
      (node (ref "SWITCH5") (pin "8") (pinfunction "1A4_8") (pintype "input"))
    )
    (net (code "93") (name "Net-(SWITCH5-2A1)") (class "Default")
      (node (ref "SL5") (pin "6") (pinfunction "6_6") (pintype "passive"))
      (node (ref "SWITCH5") (pin "11") (pinfunction "2A1_11") (pintype "input"))
    )
    (net (code "94") (name "Net-(SWITCH5-2A2)") (class "Default")
      (node (ref "SL5") (pin "5") (pinfunction "5_5") (pintype "passive"))
      (node (ref "SWITCH5") (pin "13") (pinfunction "2A2_13") (pintype "input"))
    )
    (net (code "95") (name "Net-(SWITCH6-1A1)") (class "Default")
      (node (ref "SL6") (pin "10") (pinfunction "10_10") (pintype "passive"))
      (node (ref "SWITCH6") (pin "2") (pinfunction "1A1_2") (pintype "input"))
    )
    (net (code "96") (name "Net-(SWITCH6-1A2)") (class "Default")
      (node (ref "SL6") (pin "9") (pinfunction "9_9") (pintype "passive"))
      (node (ref "SWITCH6") (pin "4") (pinfunction "1A2_4") (pintype "input"))
    )
    (net (code "97") (name "Net-(SWITCH6-1A3)") (class "Default")
      (node (ref "SL6") (pin "8") (pinfunction "8_8") (pintype "passive"))
      (node (ref "SWITCH6") (pin "6") (pinfunction "1A3_6") (pintype "input"))
    )
    (net (code "98") (name "Net-(SWITCH6-1A4)") (class "Default")
      (node (ref "SL6") (pin "7") (pinfunction "7_7") (pintype "passive"))
      (node (ref "SWITCH6") (pin "8") (pinfunction "1A4_8") (pintype "input"))
    )
    (net (code "99") (name "Net-(SWITCH6-2A1)") (class "Default")
      (node (ref "SL6") (pin "6") (pinfunction "6_6") (pintype "passive"))
      (node (ref "SWITCH6") (pin "11") (pinfunction "2A1_11") (pintype "input"))
    )
    (net (code "100") (name "Net-(SWITCH6-2A2)") (class "Default")
      (node (ref "SL6") (pin "5") (pinfunction "5_5") (pintype "passive"))
      (node (ref "SWITCH6") (pin "13") (pinfunction "2A2_13") (pintype "input"))
    )
    (net (code "101") (name "Net-(SWITCH7-1A1)") (class "Default")
      (node (ref "SL7") (pin "10") (pinfunction "10_10") (pintype "passive"))
      (node (ref "SWITCH7") (pin "2") (pinfunction "1A1_2") (pintype "input"))
    )
    (net (code "102") (name "Net-(SWITCH7-1A2)") (class "Default")
      (node (ref "SL7") (pin "9") (pinfunction "9_9") (pintype "passive"))
      (node (ref "SWITCH7") (pin "4") (pinfunction "1A2_4") (pintype "input"))
    )
    (net (code "103") (name "Net-(SWITCH7-1A3)") (class "Default")
      (node (ref "SL7") (pin "8") (pinfunction "8_8") (pintype "passive"))
      (node (ref "SWITCH7") (pin "6") (pinfunction "1A3_6") (pintype "input"))
    )
    (net (code "104") (name "Net-(SWITCH7-1A4)") (class "Default")
      (node (ref "SL7") (pin "7") (pinfunction "7_7") (pintype "passive"))
      (node (ref "SWITCH7") (pin "8") (pinfunction "1A4_8") (pintype "input"))
    )
    (net (code "105") (name "Net-(SWITCH7-2A1)") (class "Default")
      (node (ref "SL7") (pin "6") (pinfunction "6_6") (pintype "passive"))
      (node (ref "SWITCH7") (pin "11") (pinfunction "2A1_11") (pintype "input"))
    )
    (net (code "106") (name "Net-(SWITCH7-2A2)") (class "Default")
      (node (ref "SL7") (pin "5") (pinfunction "5_5") (pintype "passive"))
      (node (ref "SWITCH7") (pin "13") (pinfunction "2A2_13") (pintype "input"))
    )
    (net (code "107") (name "Net-(SWITCH8-1A1)") (class "Default")
      (node (ref "SL8") (pin "10") (pinfunction "10_10") (pintype "passive"))
      (node (ref "SWITCH8") (pin "2") (pinfunction "1A1_2") (pintype "input"))
    )
    (net (code "108") (name "Net-(SWITCH8-1A2)") (class "Default")
      (node (ref "SL8") (pin "9") (pinfunction "9_9") (pintype "passive"))
      (node (ref "SWITCH8") (pin "4") (pinfunction "1A2_4") (pintype "input"))
    )
    (net (code "109") (name "Net-(SWITCH8-1A3)") (class "Default")
      (node (ref "SL8") (pin "8") (pinfunction "8_8") (pintype "passive"))
      (node (ref "SWITCH8") (pin "6") (pinfunction "1A3_6") (pintype "input"))
    )
    (net (code "110") (name "Net-(SWITCH8-1A4)") (class "Default")
      (node (ref "SL8") (pin "7") (pinfunction "7_7") (pintype "passive"))
      (node (ref "SWITCH8") (pin "8") (pinfunction "1A4_8") (pintype "input"))
    )
    (net (code "111") (name "Net-(SWITCH8-2A1)") (class "Default")
      (node (ref "SL8") (pin "6") (pinfunction "6_6") (pintype "passive"))
      (node (ref "SWITCH8") (pin "11") (pinfunction "2A1_11") (pintype "input"))
    )
    (net (code "112") (name "Net-(SWITCH8-2A2)") (class "Default")
      (node (ref "SL8") (pin "5") (pinfunction "5_5") (pintype "passive"))
      (node (ref "SWITCH8") (pin "13") (pinfunction "2A2_13") (pintype "input"))
    )
    (net (code "113") (name "Net-(USB-D+)") (class "Default")
      (node (ref "D+") (pin "TP") (pinfunction "TP_TP") (pintype "input"))
      (node (ref "USB") (pin "D+1") (pinfunction "D+_D+1") (pintype "bidirectional"))
    )
    (net (code "114") (name "Net-(USB-D-)") (class "Default")
      (node (ref "D-") (pin "TP") (pinfunction "TP_TP") (pintype "input"))
      (node (ref "USB") (pin "D-1") (pinfunction "D-_D-1") (pintype "bidirectional"))
    )
    (net (code "115") (name "Net-(USB-USBID)") (class "Default")
      (node (ref "ID") (pin "TP") (pinfunction "TP_TP") (pintype "input"))
      (node (ref "USB") (pin "ID1") (pinfunction "USBID_ID1") (pintype "bidirectional"))
    )
    (net (code "116") (name "Net-(USB-VBUS)") (class "Default")
      (node (ref "D17") (pin "A") (pinfunction "A_A") (pintype "passive"))
      (node (ref "USB") (pin "VBUS1") (pinfunction "VBUS_VBUS1") (pintype "bidirectional"))
    )
    (net (code "117") (name "VCC") (class "Default")
      (node (ref "2-VCC") (pin "TP") (pinfunction "TP_TP") (pintype "input"))
      (node (ref "C1") (pin "1") (pinfunction "1_1") (pintype "passive"))
      (node (ref "C10") (pin "1") (pinfunction "1_1") (pintype "passive"))
      (node (ref "C12") (pin "+") (pinfunction "+_+") (pintype "passive"))
      (node (ref "C2") (pin "1") (pinfunction "1_1") (pintype "passive"))
      (node (ref "C3") (pin "1") (pinfunction "1_1") (pintype "passive"))
      (node (ref "C4") (pin "1") (pinfunction "1_1") (pintype "passive"))
      (node (ref "C5") (pin "1") (pinfunction "1_1") (pintype "passive"))
      (node (ref "C6") (pin "1") (pinfunction "1_1") (pintype "passive"))
      (node (ref "C7") (pin "1") (pinfunction "1_1") (pintype "passive"))
      (node (ref "C8") (pin "1") (pinfunction "1_1") (pintype "passive"))
      (node (ref "C9") (pin "1") (pinfunction "1_1") (pintype "passive"))
      (node (ref "CONTRAST") (pin "1") (pinfunction "A_1") (pintype "passive"))
      (node (ref "D17") (pin "C") (pinfunction "C_C") (pintype "passive"))
      (node (ref "DB_SEL") (pin "3") (pinfunction "3_3") (pintype "passive"))
      (node (ref "DB_SEL") (pin "4") (pinfunction "4_4") (pintype "passive"))
      (node (ref "IC1") (pin "2") (pinfunction "OUT_2") (pintype "passive"))
      (node (ref "IC1") (pin "TAB") (pinfunction "OUT1_TAB") (pintype "passive"))
      (node (ref "PIC") (pin "20") (pinfunction "VDD_20") (pintype "power_in"))
      (node (ref "R1") (pin "1") (pinfunction "1_1") (pintype "passive"))
      (node (ref "R16") (pin "1") (pinfunction "1_1") (pintype "passive"))
      (node (ref "R2") (pin "1") (pinfunction "1_1") (pintype "passive"))
      (node (ref "R3") (pin "1") (pinfunction "1_1") (pintype "passive"))
      (node (ref "R4") (pin "1") (pinfunction "1_1") (pintype "passive"))
      (node (ref "R5") (pin "1") (pinfunction "1_1") (pintype "passive"))
      (node (ref "R6") (pin "1") (pinfunction "1_1") (pintype "passive"))
      (node (ref "R7") (pin "1") (pinfunction "1_1") (pintype "passive"))
      (node (ref "R8") (pin "1") (pinfunction "1_1") (pintype "passive"))
      (node (ref "R9") (pin "1") (pinfunction "1_1") (pintype "passive"))
      (node (ref "SELECTOR") (pin "16") (pinfunction "VCC_16") (pintype "power_in"))
      (node (ref "SL11") (pin "1") (pinfunction "1_1") (pintype "passive"))
      (node (ref "SL12") (pin "2") (pinfunction "2_2") (pintype "passive"))
      (node (ref "SL13") (pin "15") (pinfunction "15_15") (pintype "passive"))
      (node (ref "SL13") (pin "2") (pinfunction "2_2") (pintype "passive"))
      (node (ref "SL14") (pin "3") (pinfunction "3_3") (pintype "passive"))
      (node (ref "SWITCH1") (pin "20") (pinfunction "VCC_20") (pintype "power_in"))
      (node (ref "SWITCH2") (pin "20") (pinfunction "VCC_20") (pintype "power_in"))
      (node (ref "SWITCH3") (pin "20") (pinfunction "VCC_20") (pintype "power_in"))
      (node (ref "SWITCH4") (pin "20") (pinfunction "VCC_20") (pintype "power_in"))
      (node (ref "SWITCH5") (pin "20") (pinfunction "VCC_20") (pintype "power_in"))
      (node (ref "SWITCH6") (pin "20") (pinfunction "VCC_20") (pintype "power_in"))
      (node (ref "SWITCH7") (pin "20") (pinfunction "VCC_20") (pintype "power_in"))
      (node (ref "SWITCH8") (pin "20") (pinfunction "VCC_20") (pintype "power_in"))
    )
    (net (code "118") (name "unconnected-(PIC-RB5{slash}AN13{slash}~{T1G}-Pad26)") (class "Default")
      (node (ref "PIC") (pin "26") (pinfunction "RB5/AN13/~{T1G}_26") (pintype "bidirectional"))
    )
    (net (code "119") (name "unconnected-(PIC-RC7{slash}RX{slash}DT-Pad18)") (class "Default")
      (node (ref "PIC") (pin "18") (pinfunction "RC7/RX/DT_18") (pintype "bidirectional"))
    )
    (net (code "120") (name "unconnected-(SWITCH1-2A3-Pad15)") (class "Default")
      (node (ref "SWITCH1") (pin "15") (pinfunction "2A3_15") (pintype "input"))
    )
    (net (code "121") (name "unconnected-(SWITCH1-2A4-Pad17)") (class "Default")
      (node (ref "SWITCH1") (pin "17") (pinfunction "2A4_17") (pintype "input"))
    )
    (net (code "122") (name "unconnected-(SWITCH1-2B3-Pad5)") (class "Default")
      (node (ref "SWITCH1") (pin "5") (pinfunction "2B3_5") (pintype "output"))
    )
    (net (code "123") (name "unconnected-(SWITCH1-2B4-Pad3)") (class "Default")
      (node (ref "SWITCH1") (pin "3") (pinfunction "2B4_3") (pintype "output"))
    )
    (net (code "124") (name "unconnected-(SWITCH2-2A3-Pad15)") (class "Default")
      (node (ref "SWITCH2") (pin "15") (pinfunction "2A3_15") (pintype "input"))
    )
    (net (code "125") (name "unconnected-(SWITCH2-2A4-Pad17)") (class "Default")
      (node (ref "SWITCH2") (pin "17") (pinfunction "2A4_17") (pintype "input"))
    )
    (net (code "126") (name "unconnected-(SWITCH2-2B3-Pad5)") (class "Default")
      (node (ref "SWITCH2") (pin "5") (pinfunction "2B3_5") (pintype "output"))
    )
    (net (code "127") (name "unconnected-(SWITCH2-2B4-Pad3)") (class "Default")
      (node (ref "SWITCH2") (pin "3") (pinfunction "2B4_3") (pintype "output"))
    )
    (net (code "128") (name "unconnected-(SWITCH3-2A3-Pad15)") (class "Default")
      (node (ref "SWITCH3") (pin "15") (pinfunction "2A3_15") (pintype "input"))
    )
    (net (code "129") (name "unconnected-(SWITCH3-2A4-Pad17)") (class "Default")
      (node (ref "SWITCH3") (pin "17") (pinfunction "2A4_17") (pintype "input"))
    )
    (net (code "130") (name "unconnected-(SWITCH3-2B3-Pad5)") (class "Default")
      (node (ref "SWITCH3") (pin "5") (pinfunction "2B3_5") (pintype "output"))
    )
    (net (code "131") (name "unconnected-(SWITCH3-2B4-Pad3)") (class "Default")
      (node (ref "SWITCH3") (pin "3") (pinfunction "2B4_3") (pintype "output"))
    )
    (net (code "132") (name "unconnected-(SWITCH4-2A3-Pad15)") (class "Default")
      (node (ref "SWITCH4") (pin "15") (pinfunction "2A3_15") (pintype "input"))
    )
    (net (code "133") (name "unconnected-(SWITCH4-2A4-Pad17)") (class "Default")
      (node (ref "SWITCH4") (pin "17") (pinfunction "2A4_17") (pintype "input"))
    )
    (net (code "134") (name "unconnected-(SWITCH4-2B3-Pad5)") (class "Default")
      (node (ref "SWITCH4") (pin "5") (pinfunction "2B3_5") (pintype "output"))
    )
    (net (code "135") (name "unconnected-(SWITCH4-2B4-Pad3)") (class "Default")
      (node (ref "SWITCH4") (pin "3") (pinfunction "2B4_3") (pintype "output"))
    )
    (net (code "136") (name "unconnected-(SWITCH5-2A3-Pad15)") (class "Default")
      (node (ref "SWITCH5") (pin "15") (pinfunction "2A3_15") (pintype "input"))
    )
    (net (code "137") (name "unconnected-(SWITCH5-2A4-Pad17)") (class "Default")
      (node (ref "SWITCH5") (pin "17") (pinfunction "2A4_17") (pintype "input"))
    )
    (net (code "138") (name "unconnected-(SWITCH5-2B3-Pad5)") (class "Default")
      (node (ref "SWITCH5") (pin "5") (pinfunction "2B3_5") (pintype "output"))
    )
    (net (code "139") (name "unconnected-(SWITCH5-2B4-Pad3)") (class "Default")
      (node (ref "SWITCH5") (pin "3") (pinfunction "2B4_3") (pintype "output"))
    )
    (net (code "140") (name "unconnected-(SWITCH6-2A3-Pad15)") (class "Default")
      (node (ref "SWITCH6") (pin "15") (pinfunction "2A3_15") (pintype "input"))
    )
    (net (code "141") (name "unconnected-(SWITCH6-2A4-Pad17)") (class "Default")
      (node (ref "SWITCH6") (pin "17") (pinfunction "2A4_17") (pintype "input"))
    )
    (net (code "142") (name "unconnected-(SWITCH6-2B3-Pad5)") (class "Default")
      (node (ref "SWITCH6") (pin "5") (pinfunction "2B3_5") (pintype "output"))
    )
    (net (code "143") (name "unconnected-(SWITCH6-2B4-Pad3)") (class "Default")
      (node (ref "SWITCH6") (pin "3") (pinfunction "2B4_3") (pintype "output"))
    )
    (net (code "144") (name "unconnected-(SWITCH7-2A3-Pad15)") (class "Default")
      (node (ref "SWITCH7") (pin "15") (pinfunction "2A3_15") (pintype "input"))
    )
    (net (code "145") (name "unconnected-(SWITCH7-2A4-Pad17)") (class "Default")
      (node (ref "SWITCH7") (pin "17") (pinfunction "2A4_17") (pintype "input"))
    )
    (net (code "146") (name "unconnected-(SWITCH7-2B3-Pad5)") (class "Default")
      (node (ref "SWITCH7") (pin "5") (pinfunction "2B3_5") (pintype "output"))
    )
    (net (code "147") (name "unconnected-(SWITCH7-2B4-Pad3)") (class "Default")
      (node (ref "SWITCH7") (pin "3") (pinfunction "2B4_3") (pintype "output"))
    )
    (net (code "148") (name "unconnected-(SWITCH8-2A3-Pad15)") (class "Default")
      (node (ref "SWITCH8") (pin "15") (pinfunction "2A3_15") (pintype "input"))
    )
    (net (code "149") (name "unconnected-(SWITCH8-2A4-Pad17)") (class "Default")
      (node (ref "SWITCH8") (pin "17") (pinfunction "2A4_17") (pintype "input"))
    )
    (net (code "150") (name "unconnected-(SWITCH8-2B3-Pad5)") (class "Default")
      (node (ref "SWITCH8") (pin "5") (pinfunction "2B3_5") (pintype "output"))
    )
    (net (code "151") (name "unconnected-(SWITCH8-2B4-Pad3)") (class "Default")
      (node (ref "SWITCH8") (pin "3") (pinfunction "2B4_3") (pintype "output"))
    )
  )
)
